# Perifericos.net
KiCad netlist of a schematic drawn in Altium Designer
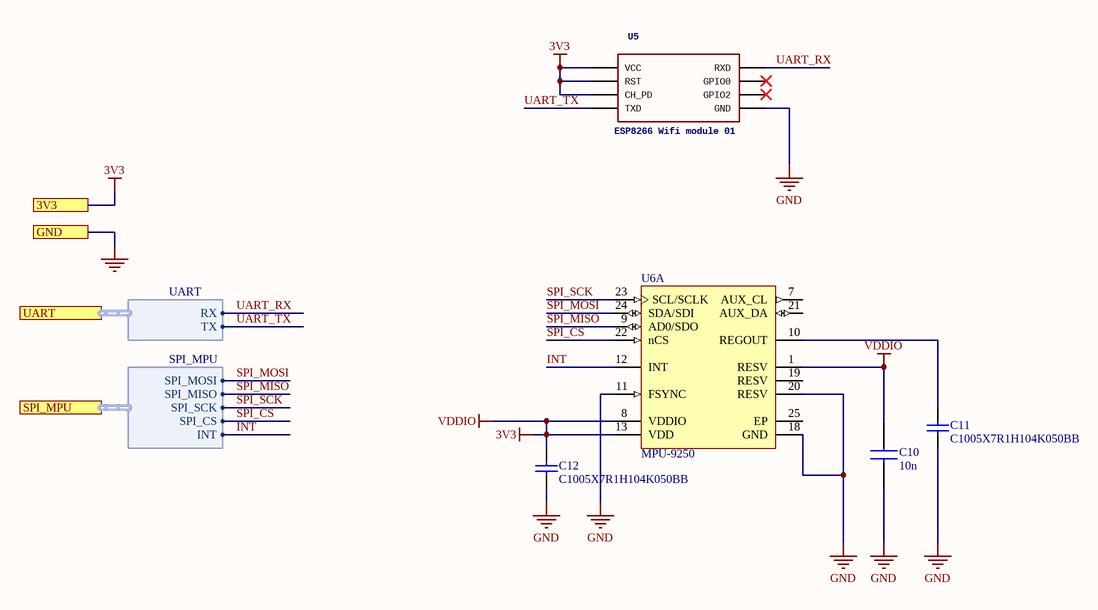
[diagram p0: Perifericos.SchDoc]

(export (version "E")
  (design (tool "Eeschema 10.0.6"))
  (components
    (comp (ref "C10")
      (value "10n")
      (footprint "SamacSys:CAPC1005X55N")
      (description "Capacitor")
      (fields
        (field (name "MANUFACTURER_PART_NUMBER") "GRM155R71E103JA01J")
        (field (name "MOUSER PART NUMBER") "81-GRM155R71E103JA1J")
      )
      (libsource (lib "*") (part "GRM155R71E103JA01J"))
    )
    (comp (ref "C11")
      (value "C1005X7R1H104K050BB")
      (footprint "TDK-C1005-2_M")
      (description "Chip Capacitor, 0.1 uF, +/- 10%, 50 V, -55 to 125 degC, 0402(1005 Metric), RoHS, Tape and Reel")
      (fields
        (field (name "PCN PART NUMBER") "MLCCPartNumberChange30/Nov/2012")
        (field (name "TOLERANCE") "±10%")
      )
      (libsource (lib "Altium Content Vault") (part "CAP-NP-2"))
    )
    (comp (ref "C12")
      (value "C1005X7R1H104K050BB")
      (footprint "TDK-C1005-2_M")
      (description "Chip Capacitor, 0.1 uF, +/- 10%, 50 V, -55 to 125 degC, 0402(1005 Metric), RoHS, Tape and Reel")
      (fields
        (field (name "PCN PART NUMBER") "MLCCPartNumberChange30/Nov/2012")
        (field (name "TOLERANCE") "±10%")
      )
      (libsource (lib "Altium Content Vault") (part "CAP-NP-2"))
    )
    (comp (ref "U5")
      (value "ESP8266 Wifi module 01")
      (footprint "ESP01")
      (description "ESP-01")
      (libsource (lib "esp8266modules") (part "ESP01"))
    )
    (comp (ref "U6")
      (value "MPU-9250")
      (footprint "INSE-QFN-24-1700X1540TP_L")
      (description "9-axis MotionTracking device, 2.4 to 3,6 V, -40 to 85 degC, 24-Pin QFN, RoHS, Tape and Reel")
      (fields (field (name "MANUFACTURER") "InvenSense"))
      (libsource (lib "MPU-9250") (part "CMP-2100-03657-1"))
    )
  )
  (nets
    (net (code "3") (name "/INT") (class "Default")
      (node (ref "U6") (pin "12") (pinfunction "INT_12") (pintype "tri_state"))
    )
    (net (code "4") (name "/SPI_CS") (class "Default")
      (node (ref "U6") (pin "22") (pinfunction "nCS_22") (pintype "input"))
    )
    (net (code "5") (name "/SPI_MISO") (class "Default")
      (node (ref "U6") (pin "9") (pinfunction "AD0/SDO_9") (pintype "bidirectional"))
    )
    (net (code "6") (name "/SPI_MOSI") (class "Default")
      (node (ref "U6") (pin "24") (pinfunction "SDA/SDI_24") (pintype "bidirectional"))
    )
    (net (code "7") (name "/SPI_SCK") (class "Default")
      (node (ref "U6") (pin "23") (pinfunction "SCL/SCLK_23") (pintype "input"))
    )
    (net (code "8") (name "/UART_RX") (class "Default")
      (node (ref "U5") (pin "RX") (pinfunction "RXD_RX") (pintype "passive"))
    )
    (net (code "9") (name "/UART_TX") (class "Default")
      (node (ref "U5") (pin "TX") (pinfunction "TXD_TX") (pintype "passive"))
    )
    (net (code "12") (name "0") (class "Default")
      (node (ref "C10") (pin "2") (pinfunction "2_2") (pintype "passive"))
      (node (ref "C11") (pin "1") (pinfunction "1_1") (pintype "passive"))
      (node (ref "C12") (pin "1") (pinfunction "1_1") (pintype "passive"))
      (node (ref "U5") (pin "GND") (pinfunction "GND_GND") (pintype "passive"))
      (node (ref "U6") (pin "11") (pinfunction "FSYNC_11") (pintype "input"))
      (node (ref "U6") (pin "18") (pinfunction "GND_18") (pintype "power_in"))
      (node (ref "U6") (pin "20") (pinfunction "RESV_20") (pintype "power_in"))
    )
    (net (code "13") (name "3V3") (class "Default")
      (node (ref "C10") (pin "1") (pinfunction "1_1") (pintype "passive"))
      (node (ref "C12") (pin "2") (pinfunction "2_2") (pintype "passive"))
      (node (ref "U5") (pin "CH_PD") (pinfunction "CH_PD_CH_PD") (pintype "passive"))
      (node (ref "U5") (pin "RST") (pinfunction "RST_RST") (pintype "passive"))
      (node (ref "U5") (pin "VCC") (pinfunction "VCC_VCC") (pintype "passive"))
      (node (ref "U6") (pin "1") (pinfunction "RESV_1") (pintype "power_in"))
      (node (ref "U6") (pin "13") (pinfunction "VDD_13") (pintype "power_in"))
      (node (ref "U6") (pin "8") (pinfunction "VDDIO_8") (pintype "power_in"))
    )
    (net (code "14") (name "Net-(U6A-REGOUT)") (class "Default")
      (node (ref "C11") (pin "2") (pinfunction "2_2") (pintype "passive"))
      (node (ref "U6") (pin "10") (pinfunction "REGOUT_10") (pintype "passive"))
    )
    (net (code "15") (name "unconnected-(U5-PadGPIO0)") (class "Default")
      (node (ref "U5") (pin "GPIO0") (pinfunction "GPIO0_GPIO0") (pintype "passive+no_connect"))
    )
    (net (code "16") (name "unconnected-(U5-PadGPIO2)") (class "Default")
      (node (ref "U5") (pin "GPIO2") (pinfunction "GPIO2_GPIO2") (pintype "passive+no_connect"))
    )
    (net (code "17") (name "unconnected-(U6A-AUX_CL-Pad7)") (class "Default")
      (node (ref "U6") (pin "7") (pinfunction "AUX_CL_7") (pintype "output"))
    )
    (net (code "18") (name "unconnected-(U6A-AUX_DA-Pad21)") (class "Default")
      (node (ref "U6") (pin "21") (pinfunction "AUX_DA_21") (pintype "bidirectional"))
    )
    (net (code "19") (name "unconnected-(U6A-EP-Pad25)") (class "Default")
      (node (ref "U6") (pin "25") (pinfunction "EP_25") (pintype "passive"))
    )
    (net (code "20") (name "unconnected-(U6A-RESV-Pad19)") (class "Default")
      (node (ref "U6") (pin "19") (pinfunction "RESV_19") (pintype "passive"))
    )
  )
)
